# Page_Tete.net
KiCad netlist of a schematic drawn in Altium Designer
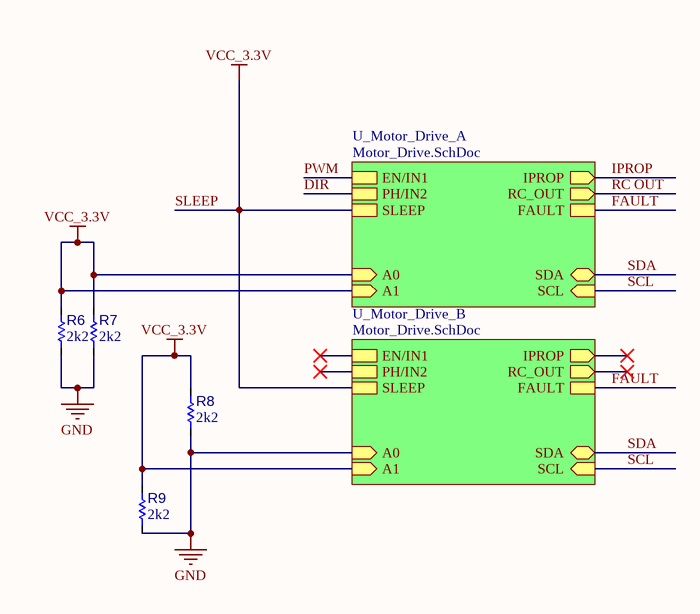
[diagram p0: Page_Tete.SchDoc]

(export (version "E")
  (design (tool "Eeschema 10.0.6"))
  (components
    (comp (ref "R6")
      (value "2k2")
      (footprint "R_1005[0402]")
      (description "Resistor type 1")
      (fields (field (name "TOLERANCE") "1%") (field (name "Comment") "Res 2k2 1% 0402"))
      (libsource (lib "TEP_243-Altium_DBLib") (part "resistor"))
    )
    (comp (ref "R7")
      (value "2k2")
      (footprint "R_1005[0402]")
      (description "Resistor type 1")
      (fields (field (name "TOLERANCE") "1%") (field (name "Comment") "Res 2k2 1% 0402"))
      (libsource (lib "TEP_243-Altium_DBLib") (part "resistor"))
    )
    (comp (ref "R8")
      (value "2k2")
      (footprint "R_1005[0402]")
      (description "Resistor type 1")
      (fields (field (name "TOLERANCE") "1%") (field (name "Comment") "Res 2k2 1% 0402"))
      (libsource (lib "TEP_243-Altium_DBLib") (part "resistor"))
    )
    (comp (ref "R9")
      (value "2k2")
      (footprint "R_1005[0402]")
      (description "Resistor type 1")
      (fields (field (name "TOLERANCE") "1%") (field (name "Comment") "Res 2k2 1% 0402"))
      (libsource (lib "TEP_243-Altium_DBLib") (part "resistor"))
    )
  )
  (nets
    (net (code "12") (name "GND") (class "Default")
      (node (ref "R6") (pin "1") (pinfunction "1_1") (pintype "passive"))
      (node (ref "R7") (pin "1") (pinfunction "1_1") (pintype "passive"))
      (node (ref "R8") (pin "1") (pinfunction "1_1") (pintype "passive"))
      (node (ref "R9") (pin "1") (pinfunction "1_1") (pintype "passive"))
    )
    (net (code "13") (name "VCC_3.3V") (class "Default")
      (node (ref "R6") (pin "2") (pinfunction "2_2") (pintype "passive"))
      (node (ref "R7") (pin "2") (pinfunction "2_2") (pintype "passive"))
      (node (ref "R8") (pin "2") (pinfunction "2_2") (pintype "passive"))
      (node (ref "R9") (pin "2") (pinfunction "2_2") (pintype "passive"))
    )
  )
)
